# r4.net
KiCad netlist of a schematic drawn in EasyEDA
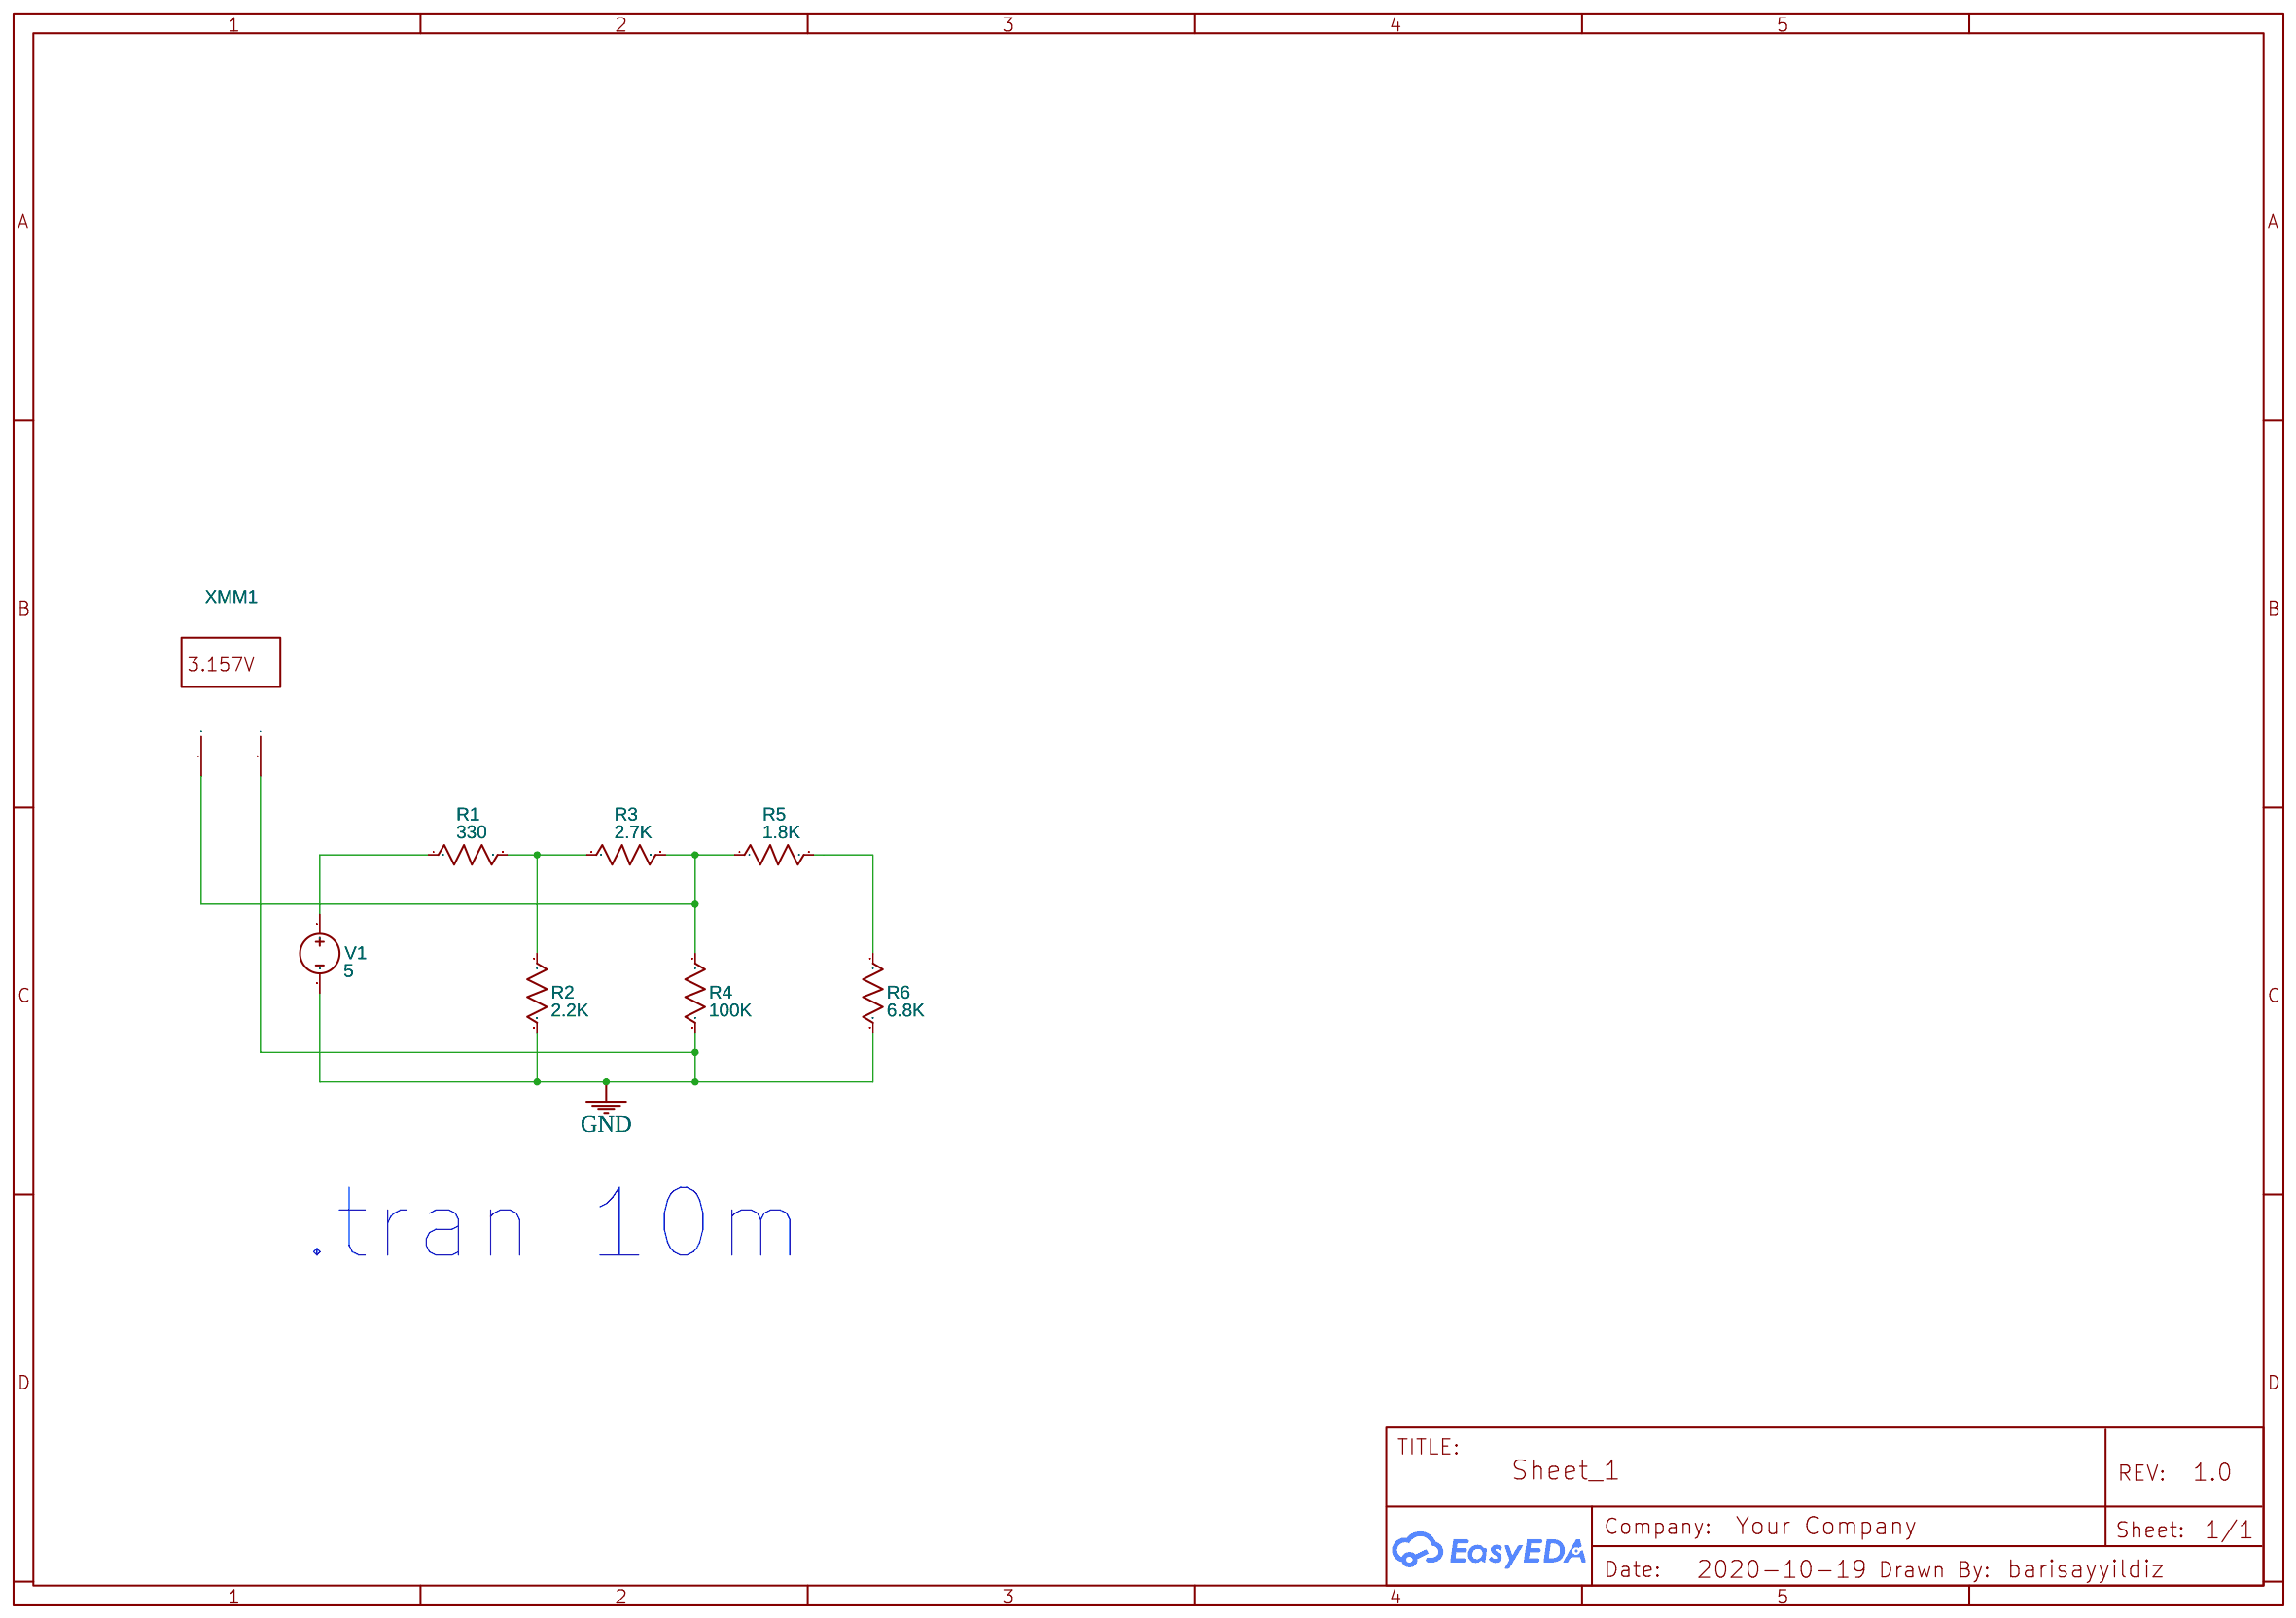
[diagram p0: schematic sheet]

(export (version "E")
  (design (tool "Eeschema 10.0.6"))
  (components
    (comp (ref "R1") (value "330") (libsource (lib "") (part "Resistor_US_1")))
    (comp (ref "R2") (value "2.2K") (libsource (lib "") (part "Resistor_US")))
    (comp (ref "R3") (value "2.7K") (libsource (lib "") (part "Resistor_US_1")))
    (comp (ref "R4") (value "100K") (libsource (lib "") (part "Resistor_US")))
    (comp (ref "R5") (value "1.8K") (libsource (lib "") (part "Resistor_US_1")))
    (comp (ref "R6") (value "6.8K") (libsource (lib "") (part "Resistor_US")))
    (comp (ref "V1") (value "5") (libsource (lib "") (part "VDC")))
    (comp (ref "XMM1") (value "Multimeter") (libsource (lib "") (part "MULTIMETER")))
  )
  (nets
    (net (code "1") (name "GND") (class "Default")
      (node (ref "R2") (pin "2") (pinfunction "2_2") (pintype "unspecified"))
      (node (ref "R4") (pin "2") (pinfunction "2_2") (pintype "unspecified"))
      (node (ref "R6") (pin "2") (pinfunction "2_2") (pintype "unspecified"))
      (node (ref "V1") (pin "2") (pinfunction "2_2") (pintype "unspecified"))
      (node (ref "XMM1") (pin "2") (pinfunction "I_2") (pintype "unspecified"))
    )
    (net (code "2") (name "Net-(R1-Pad1)") (class "Default")
      (node (ref "R1") (pin "1") (pinfunction "1_1") (pintype "unspecified"))
      (node (ref "V1") (pin "1") (pinfunction "1_1") (pintype "unspecified"))
    )
    (net (code "3") (name "Net-(R1-Pad2)") (class "Default")
      (node (ref "R1") (pin "2") (pinfunction "2_2") (pintype "unspecified"))
      (node (ref "R2") (pin "1") (pinfunction "1_1") (pintype "unspecified"))
      (node (ref "R3") (pin "1") (pinfunction "1_1") (pintype "unspecified"))
    )
    (net (code "4") (name "Net-(R5-Pad2)") (class "Default")
      (node (ref "R5") (pin "2") (pinfunction "2_2") (pintype "unspecified"))
      (node (ref "R6") (pin "1") (pinfunction "1_1") (pintype "unspecified"))
    )
    (net (code "5") (name "Net-(XMM1-+)") (class "Default")
      (node (ref "R3") (pin "2") (pinfunction "2_2") (pintype "unspecified"))
      (node (ref "R4") (pin "1") (pinfunction "1_1") (pintype "unspecified"))
      (node (ref "R5") (pin "1") (pinfunction "1_1") (pintype "unspecified"))
      (node (ref "XMM1") (pin "1") (pinfunction "+_1") (pintype "unspecified"))
    )
  )
)
